# ISP_breakout.net
KiCad netlist of a schematic drawn in EAGLE
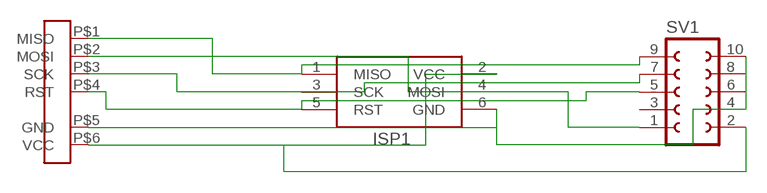
[diagram p0: schematic, sheet 1]

(export (version "E")
  (design (tool "Eeschema 10.0.6"))
  (components
    (comp (ref "ISP1")
      (value "AVRISP-6")
      (footprint "eagle-import:AVRISP")
      (libsource (lib "eagle-import") (part "AVRISP-6"))
    )
    (comp (ref "SV1")
      (value "FE05-2")
      (footprint "eagle-import:FE05-2")
      (libsource (lib "eagle-import") (part "FE05-2"))
    )
    (comp (ref "U$1")
      (value "LIN_ISP")
      (footprint "eagle-import:LINEAR_ISP")
      (libsource (lib "eagle-import") (part "LIN_ISP"))
    )
  )
  (nets
    (net (code "1") (name "Net-(ISP1-GND)") (class "Default")
      (node (ref "ISP1") (pin "6") (pinfunction "GND_6") (pintype "power_in"))
      (node (ref "SV1") (pin "10") (pinfunction "10_10") (pintype "passive"))
      (node (ref "SV1") (pin "4") (pinfunction "4_4") (pintype "passive"))
      (node (ref "SV1") (pin "6") (pinfunction "6_6") (pintype "passive"))
      (node (ref "SV1") (pin "8") (pinfunction "8_8") (pintype "passive"))
      (node (ref "U$1") (pin "P$5") (pinfunction "GND_P$5") (pintype "bidirectional"))
    )
    (net (code "2") (name "Net-(ISP1-MISO)") (class "Default")
      (node (ref "ISP1") (pin "1") (pinfunction "MISO_1") (pintype "input"))
      (node (ref "SV1") (pin "9") (pinfunction "9_9") (pintype "passive"))
      (node (ref "U$1") (pin "P$1") (pinfunction "MISO_P$1") (pintype "bidirectional"))
    )
    (net (code "3") (name "Net-(ISP1-MOSI)") (class "Default")
      (node (ref "ISP1") (pin "4") (pinfunction "MOSI_4") (pintype "output"))
      (node (ref "SV1") (pin "1") (pinfunction "1_1") (pintype "passive"))
      (node (ref "U$1") (pin "P$2") (pinfunction "MOSI_P$2") (pintype "bidirectional"))
    )
    (net (code "4") (name "Net-(ISP1-RST)") (class "Default")
      (node (ref "ISP1") (pin "5") (pinfunction "RST_5") (pintype "output"))
      (node (ref "SV1") (pin "5") (pinfunction "5_5") (pintype "passive"))
      (node (ref "U$1") (pin "P$4") (pinfunction "RST_P$4") (pintype "bidirectional"))
    )
    (net (code "5") (name "Net-(ISP1-SCK)") (class "Default")
      (node (ref "ISP1") (pin "3") (pinfunction "SCK_3") (pintype "output"))
      (node (ref "SV1") (pin "7") (pinfunction "7_7") (pintype "passive"))
      (node (ref "U$1") (pin "P$3") (pinfunction "SCK_P$3") (pintype "bidirectional"))
    )
    (net (code "6") (name "Net-(ISP1-VCC)") (class "Default")
      (node (ref "ISP1") (pin "2") (pinfunction "VCC_2") (pintype "power_in"))
      (node (ref "SV1") (pin "2") (pinfunction "2_2") (pintype "passive"))
      (node (ref "U$1") (pin "P$6") (pinfunction "VCC_P$6") (pintype "bidirectional"))
    )
    (net (code "7") (name "unconnected-(SV1-Pad3)") (class "Default")
      (node (ref "SV1") (pin "3") (pinfunction "3_3") (pintype "passive"))
    )
  )
)
